# Satellite_Transceiver_Function_Board__Sw.net
KiCad netlist of a schematic drawn in EAGLE
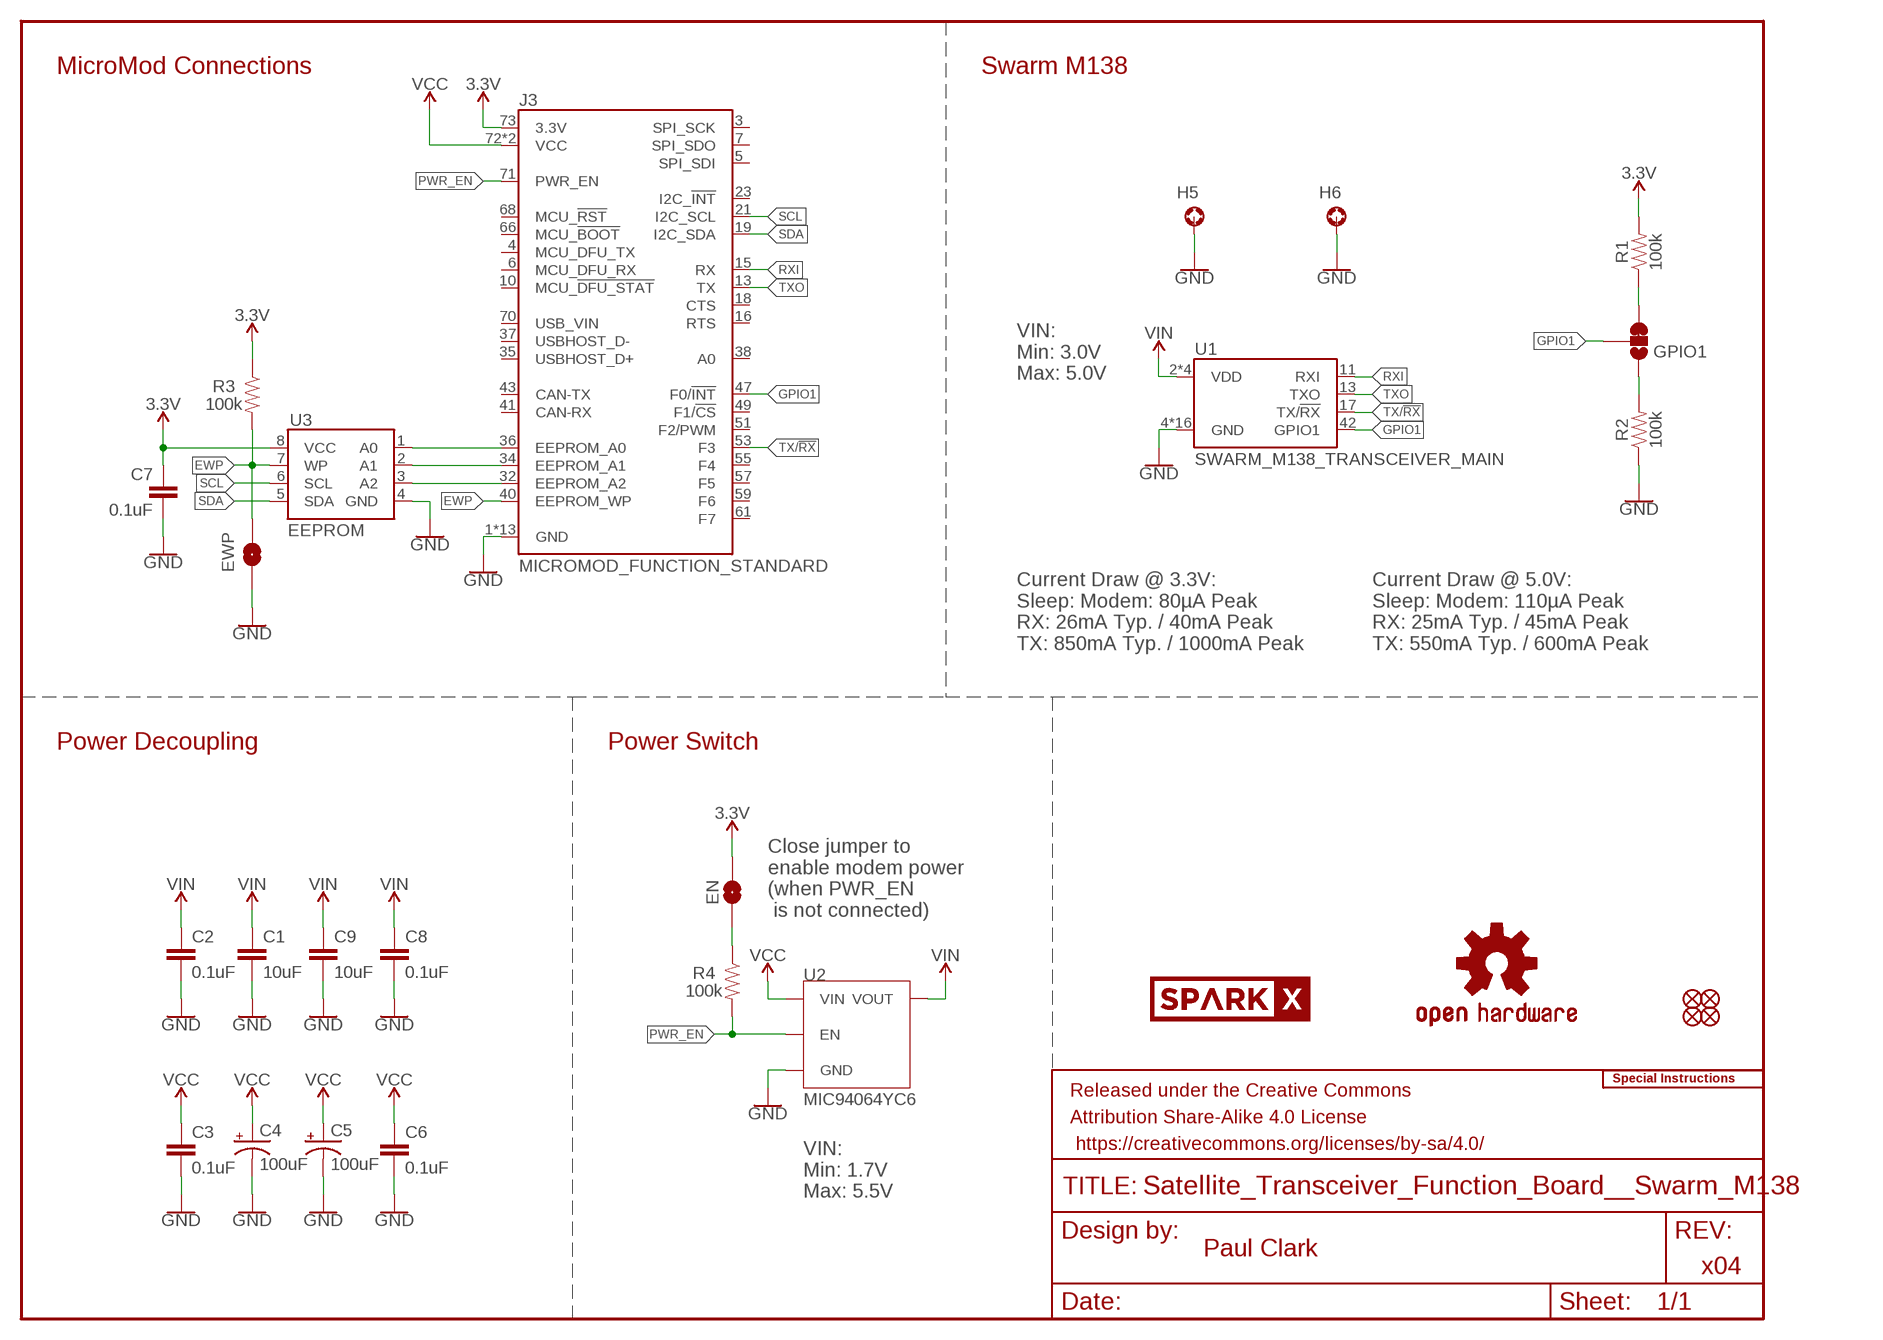
[diagram p0: schematic, sheet 1]

(export (version "E")
  (design (tool "Eeschema 10.0.6"))
  (components
    (comp (ref "C1")
      (value "10uF")
      (footprint "eagle-import:0603")
      (libsource (lib "eagle-import") (part "10UF-0603-6.3V-20%"))
    )
    (comp (ref "C2")
      (value "0.1uF")
      (footprint "eagle-import:0603")
      (libsource (lib "eagle-import") (part "0.1UF-0603-25V-5%"))
    )
    (comp (ref "C3")
      (value "0.1uF")
      (footprint "eagle-import:0603")
      (libsource (lib "eagle-import") (part "0.1UF-0603-25V-5%"))
    )
    (comp (ref "C4")
      (value "100uF")
      (footprint "eagle-import:EIA3528")
      (libsource (lib "eagle-import") (part "100UF-POLAR-EIA3528-10V-20%(TANT)"))
    )
    (comp (ref "C5")
      (value "100uF")
      (footprint "eagle-import:EIA3528")
      (libsource (lib "eagle-import") (part "100UF-POLAR-EIA3528-10V-20%(TANT)"))
    )
    (comp (ref "C6")
      (value "0.1uF")
      (footprint "eagle-import:0603")
      (libsource (lib "eagle-import") (part "0.1UF-0603-25V-5%"))
    )
    (comp (ref "C7")
      (value "0.1uF")
      (footprint "eagle-import:0603")
      (libsource (lib "eagle-import") (part "0.1UF-0603-25V-5%"))
    )
    (comp (ref "C8")
      (value "0.1uF")
      (footprint "eagle-import:0603")
      (libsource (lib "eagle-import") (part "0.1UF-0603-25V-5%"))
    )
    (comp (ref "C9")
      (value "10uF")
      (footprint "eagle-import:0603")
      (libsource (lib "eagle-import") (part "10UF-0603-6.3V-20%"))
    )
    (comp (ref "EN")
      (value "JUMPER-SMT_2_NO_SILK")
      (footprint "eagle-import:SMT-JUMPER_2_NO_SILK")
      (libsource (lib "eagle-import") (part "JUMPER-SMT_2_NO_SILK"))
    )
    (comp (ref "EWP")
      (value "JUMPER-SMT_2_NO_SILK")
      (footprint "eagle-import:SMT-JUMPER_2_NO_SILK")
      (libsource (lib "eagle-import") (part "JUMPER-SMT_2_NO_SILK"))
    )
    (comp (ref "FD1")
      (value "FIDUCIAL1X2")
      (footprint "eagle-import:FIDUCIAL-1X2")
      (libsource (lib "eagle-import") (part "FIDUCIAL1X2"))
    )
    (comp (ref "FD2")
      (value "FIDUCIAL1X2")
      (footprint "eagle-import:FIDUCIAL-1X2")
      (libsource (lib "eagle-import") (part "FIDUCIAL1X2"))
    )
    (comp (ref "FD3")
      (value "FIDUCIAL1X2")
      (footprint "eagle-import:FIDUCIAL-1X2")
      (libsource (lib "eagle-import") (part "FIDUCIAL1X2"))
    )
    (comp (ref "FD4")
      (value "FIDUCIAL1X2")
      (footprint "eagle-import:FIDUCIAL-1X2")
      (libsource (lib "eagle-import") (part "FIDUCIAL1X2"))
    )
    (comp (ref "FRAME1")
      (value "FRAME-LETTER")
      (footprint "eagle-import:CREATIVE_COMMONS")
      (libsource (lib "eagle-import") (part "FRAME-LETTER"))
    )
    (comp (ref "GPIO1")
      (value "JUMPER-SMT_3_1-NC_TRACE_SILK")
      (footprint "eagle-import:SMT-JUMPER_3_1-NC_TRACE_SILK")
      (libsource (lib "eagle-import") (part "JUMPER-SMT_3_1-NC_TRACE_SILK"))
    )
    (comp (ref "H5")
      (value "STAND-OFF-REFLOW-M2.5_1.5MM_TALL")
      (footprint "eagle-import:STAND-OFF-REFLOW-M2.5")
      (libsource (lib "eagle-import") (part "STAND-OFF-REFLOW-M2.5_1.5MM_TALL"))
    )
    (comp (ref "H6")
      (value "STAND-OFF-REFLOW-M2.5_1.5MM_TALL")
      (footprint "eagle-import:STAND-OFF-REFLOW-M2.5")
      (libsource (lib "eagle-import") (part "STAND-OFF-REFLOW-M2.5_1.5MM_TALL"))
    )
    (comp (ref "J3")
      (value "MICROMOD_FUNCTION_STANDARD")
      (footprint "eagle-import:M.2-CARD-E-22_FUNCTION_STANDARD")
      (libsource (lib "eagle-import") (part "MICROMOD_FUNCTION_STANDARD"))
    )
    (comp (ref "LOGO1")
      (value "SPECIAL_INSTRUCTIONS-ORDERING")
      (footprint "eagle-import:ORDERING_INSTRUCTIONS")
      (libsource (lib "eagle-import") (part "SPECIAL_INSTRUCTIONS-ORDERING"))
    )
    (comp (ref "LOGO2")
      (value "OSHW-LOGOS")
      (footprint "eagle-import:OSHW-LOGO-S")
      (libsource (lib "eagle-import") (part "OSHW-LOGOS"))
    )
    (comp (ref "R1")
      (value "100k")
      (footprint "eagle-import:0603")
      (libsource (lib "eagle-import") (part "100KOHM-0603-1/10W-1%"))
    )
    (comp (ref "R2")
      (value "100k")
      (footprint "eagle-import:0603")
      (libsource (lib "eagle-import") (part "100KOHM-0603-1/10W-1%"))
    )
    (comp (ref "R3")
      (value "100k")
      (footprint "eagle-import:0603")
      (libsource (lib "eagle-import") (part "100KOHM-0603-1/10W-1%"))
    )
    (comp (ref "R4")
      (value "100k")
      (footprint "eagle-import:0603")
      (libsource (lib "eagle-import") (part "100KOHM-0603-1/10W-1%"))
    )
    (comp (ref "U$1")
      (value "SPARKX-LOGO5")
      (footprint "eagle-import:SPARKX-LARGE")
      (libsource (lib "eagle-import") (part "SPARKX-LOGO5"))
    )
    (comp (ref "U$2")
      (value "SPARKX-LOGO5")
      (footprint "eagle-import:SPARKX-LARGE")
      (libsource (lib "eagle-import") (part "SPARKX-LOGO5"))
    )
    (comp (ref "U1")
      (value "SWARM_M138_TRANSCEIVER_MAIN")
      (footprint "eagle-import:M.2-SWARM-M138-A")
      (libsource (lib "eagle-import") (part "SWARM_M138_TRANSCEIVER_MAIN"))
    )
    (comp (ref "U2")
      (value "MIC94064YC6")
      (footprint "eagle-import:SC-70-6")
      (libsource (lib "eagle-import") (part "MIC94064/5_MIC94064YC6"))
    )
    (comp (ref "U3")
      (value "EEPROM")
      (footprint "eagle-import:SO08")
      (libsource (lib "eagle-import") (part "EEPROM-I2C512K"))
    )
  )
  (nets
    (net (code "1") (name "/TX{slash}~{RX}") (class "Default")
      (node (ref "J3") (pin "53") (pinfunction "F3_53") (pintype "bidirectional"))
      (node (ref "U1") (pin "17") (pinfunction "TX/~{RX}_17") (pintype "output"))
    )
    (net (code "2") (name "3.3V") (class "Default")
      (node (ref "C7") (pin "1") (pinfunction "1_1") (pintype "passive"))
      (node (ref "EN") (pin "2") (pinfunction "2_2") (pintype "passive"))
      (node (ref "J3") (pin "73") (pinfunction "3.3V_73") (pintype "bidirectional"))
      (node (ref "R1") (pin "2") (pinfunction "2_2") (pintype "passive"))
      (node (ref "R3") (pin "1") (pinfunction "1_1") (pintype "passive"))
      (node (ref "U3") (pin "8") (pinfunction "VCC_8") (pintype "power_in"))
    )
    (net (code "3") (name "EWP") (class "Default")
      (node (ref "EWP") (pin "2") (pinfunction "2_2") (pintype "passive"))
      (node (ref "J3") (pin "40") (pinfunction "EEPROM_WP_40") (pintype "bidirectional"))
      (node (ref "R3") (pin "2") (pinfunction "2_2") (pintype "passive"))
      (node (ref "U3") (pin "7") (pinfunction "WP_7") (pintype "bidirectional"))
    )
    (net (code "4") (name "GND") (class "Default")
      (node (ref "C1") (pin "2") (pinfunction "2_2") (pintype "passive"))
      (node (ref "C2") (pin "2") (pinfunction "2_2") (pintype "passive"))
      (node (ref "C3") (pin "2") (pinfunction "2_2") (pintype "passive"))
      (node (ref "C4") (pin "C") (pinfunction "-_C") (pintype "passive"))
      (node (ref "C5") (pin "C") (pinfunction "-_C") (pintype "passive"))
      (node (ref "C6") (pin "2") (pinfunction "2_2") (pintype "passive"))
      (node (ref "C7") (pin "2") (pinfunction "2_2") (pintype "passive"))
      (node (ref "C8") (pin "2") (pinfunction "2_2") (pintype "passive"))
      (node (ref "C9") (pin "2") (pinfunction "2_2") (pintype "passive"))
      (node (ref "EWP") (pin "1") (pinfunction "1_1") (pintype "passive"))
      (node (ref "H5") (pin "1") (pinfunction "1_1") (pintype "bidirectional"))
      (node (ref "H6") (pin "1") (pinfunction "1_1") (pintype "bidirectional"))
      (node (ref "J3") (pin "1") (pinfunction "GND_1") (pintype "bidirectional"))
      (node (ref "J3") (pin "2") (pinfunction "GND_2") (pintype "bidirectional"))
      (node (ref "J3") (pin "33") (pinfunction "GND_33") (pintype "bidirectional"))
      (node (ref "J3") (pin "39") (pinfunction "GND_39") (pintype "bidirectional"))
      (node (ref "J3") (pin "45") (pinfunction "GND_45") (pintype "bidirectional"))
      (node (ref "J3") (pin "75") (pinfunction "GND_75") (pintype "bidirectional"))
      (node (ref "J3") (pin "8") (pinfunction "GND_8") (pintype "bidirectional"))
      (node (ref "J3") (pin "GND1") (pinfunction "GND_GND1") (pintype "bidirectional"))
      (node (ref "J3") (pin "GND2") (pinfunction "GND_GND2") (pintype "bidirectional"))
      (node (ref "J3") (pin "GND3") (pinfunction "GND_GND3") (pintype "bidirectional"))
      (node (ref "J3") (pin "GND4") (pinfunction "GND_GND4") (pintype "bidirectional"))
      (node (ref "J3") (pin "GND5") (pinfunction "GND_GND5") (pintype "bidirectional"))
      (node (ref "J3") (pin "GND6") (pinfunction "GND_GND6") (pintype "bidirectional"))
      (node (ref "R2") (pin "1") (pinfunction "1_1") (pintype "passive"))
      (node (ref "U1") (pin "15") (pinfunction "GND_15") (pintype "power_in"))
      (node (ref "U1") (pin "18") (pinfunction "GND_18") (pintype "power_in"))
      (node (ref "U1") (pin "21") (pinfunction "GND_21") (pintype "power_in"))
      (node (ref "U1") (pin "26") (pinfunction "GND_26") (pintype "power_in"))
      (node (ref "U1") (pin "27") (pinfunction "GND_27") (pintype "power_in"))
      (node (ref "U1") (pin "29") (pinfunction "GND_29") (pintype "power_in"))
      (node (ref "U1") (pin "34") (pinfunction "GND_34") (pintype "power_in"))
      (node (ref "U1") (pin "35") (pinfunction "GND_35") (pintype "power_in"))
      (node (ref "U1") (pin "37") (pinfunction "GND_37") (pintype "power_in"))
      (node (ref "U1") (pin "4") (pinfunction "GND_4") (pintype "power_in"))
      (node (ref "U1") (pin "40") (pinfunction "GND_40") (pintype "power_in"))
      (node (ref "U1") (pin "43") (pinfunction "GND_43") (pintype "power_in"))
      (node (ref "U1") (pin "50") (pinfunction "GND_50") (pintype "power_in"))
      (node (ref "U1") (pin "9") (pinfunction "GND_9") (pintype "power_in"))
      (node (ref "U1") (pin "A1") (pinfunction "GND_A1") (pintype "power_in"))
      (node (ref "U1") (pin "A2") (pinfunction "GND_A2") (pintype "power_in"))
      (node (ref "U2") (pin "2") (pinfunction "GND_2") (pintype "power_in"))
      (node (ref "U2") (pin "5") (pinfunction "GND_5") (pintype "power_in"))
      (node (ref "U3") (pin "4") (pinfunction "GND_4") (pintype "power_in"))
    )
    (net (code "5") (name "GPIO1") (class "Default")
      (node (ref "GPIO1") (pin "2") (pinfunction "2_2") (pintype "passive"))
      (node (ref "J3") (pin "47") (pinfunction "F0/~{INT}_47") (pintype "bidirectional"))
      (node (ref "U1") (pin "42") (pinfunction "GPIO1_42") (pintype "bidirectional"))
    )
    (net (code "6") (name "Net-(EN-Pad1)") (class "Default")
      (node (ref "EN") (pin "1") (pinfunction "1_1") (pintype "passive"))
      (node (ref "R4") (pin "1") (pinfunction "1_1") (pintype "passive"))
    )
    (net (code "7") (name "Net-(GPIO1-Pad1)") (class "Default")
      (node (ref "GPIO1") (pin "1") (pinfunction "1_1") (pintype "passive"))
      (node (ref "R2") (pin "2") (pinfunction "2_2") (pintype "passive"))
    )
    (net (code "8") (name "Net-(GPIO1-Pad3)") (class "Default")
      (node (ref "GPIO1") (pin "3") (pinfunction "3_3") (pintype "passive"))
      (node (ref "R1") (pin "1") (pinfunction "1_1") (pintype "passive"))
    )
    (net (code "9") (name "Net-(J3-EEPROM_A0)") (class "Default")
      (node (ref "J3") (pin "36") (pinfunction "EEPROM_A0_36") (pintype "bidirectional"))
      (node (ref "U3") (pin "1") (pinfunction "A0_1") (pintype "bidirectional"))
    )
    (net (code "10") (name "Net-(J3-EEPROM_A1)") (class "Default")
      (node (ref "J3") (pin "34") (pinfunction "EEPROM_A1_34") (pintype "bidirectional"))
      (node (ref "U3") (pin "2") (pinfunction "A1_2") (pintype "bidirectional"))
    )
    (net (code "11") (name "Net-(J3-EEPROM_A2)") (class "Default")
      (node (ref "J3") (pin "32") (pinfunction "EEPROM_A2_32") (pintype "bidirectional"))
      (node (ref "U3") (pin "3") (pinfunction "A2_3") (pintype "bidirectional"))
    )
    (net (code "12") (name "PWR_EN") (class "Default")
      (node (ref "J3") (pin "71") (pinfunction "PWR_EN_71") (pintype "bidirectional"))
      (node (ref "R4") (pin "2") (pinfunction "2_2") (pintype "passive"))
      (node (ref "U2") (pin "3") (pinfunction "EN_3") (pintype "input"))
    )
    (net (code "13") (name "RXI") (class "Default")
      (node (ref "J3") (pin "15") (pinfunction "RX_15") (pintype "bidirectional"))
      (node (ref "U1") (pin "11") (pinfunction "RXI_11") (pintype "input"))
    )
    (net (code "14") (name "SCL") (class "Default")
      (node (ref "J3") (pin "21") (pinfunction "I2C_SCL_21") (pintype "bidirectional"))
      (node (ref "U3") (pin "6") (pinfunction "SCL_6") (pintype "bidirectional"))
    )
    (net (code "15") (name "SDA") (class "Default")
      (node (ref "J3") (pin "19") (pinfunction "I2C_SDA_19") (pintype "bidirectional"))
      (node (ref "U3") (pin "5") (pinfunction "SDA_5") (pintype "bidirectional"))
    )
    (net (code "16") (name "TXO") (class "Default")
      (node (ref "J3") (pin "13") (pinfunction "TX_13") (pintype "bidirectional"))
      (node (ref "U1") (pin "13") (pinfunction "TXO_13") (pintype "output"))
    )
    (net (code "17") (name "VCC") (class "Default")
      (node (ref "C3") (pin "1") (pinfunction "1_1") (pintype "passive"))
      (node (ref "C4") (pin "A") (pinfunction "+_A") (pintype "passive"))
      (node (ref "C5") (pin "A") (pinfunction "+_A") (pintype "passive"))
      (node (ref "C6") (pin "1") (pinfunction "1_1") (pintype "passive"))
      (node (ref "J3") (pin "72") (pinfunction "VCC_72") (pintype "bidirectional"))
      (node (ref "J3") (pin "74") (pinfunction "VCC_74") (pintype "bidirectional"))
      (node (ref "U2") (pin "4") (pinfunction "VIN_4") (pintype "power_in"))
    )
    (net (code "18") (name "VIN") (class "Default")
      (node (ref "C1") (pin "1") (pinfunction "1_1") (pintype "passive"))
      (node (ref "C2") (pin "1") (pinfunction "1_1") (pintype "passive"))
      (node (ref "C8") (pin "1") (pinfunction "1_1") (pintype "passive"))
      (node (ref "C9") (pin "1") (pinfunction "1_1") (pintype "passive"))
      (node (ref "U1") (pin "2") (pinfunction "VDD_2") (pintype "power_in"))
      (node (ref "U1") (pin "39") (pinfunction "VDD_39") (pintype "power_in"))
      (node (ref "U1") (pin "41") (pinfunction "VDD_41") (pintype "power_in"))
      (node (ref "U1") (pin "52") (pinfunction "VDD_52") (pintype "power_in"))
      (node (ref "U2") (pin "1") (pinfunction "VOUT_1") (pintype "power_in"))
    )
    (net (code "19") (name "unconnected-(J3-A0-Pad38)") (class "Default")
      (node (ref "J3") (pin "38") (pinfunction "A0_38") (pintype "bidirectional"))
    )
    (net (code "20") (name "unconnected-(J3-CAN-RX-Pad41)") (class "Default")
      (node (ref "J3") (pin "41") (pinfunction "CAN-RX_41") (pintype "bidirectional"))
    )
    (net (code "21") (name "unconnected-(J3-CAN-TX-Pad43)") (class "Default")
      (node (ref "J3") (pin "43") (pinfunction "CAN-TX_43") (pintype "bidirectional"))
    )
    (net (code "22") (name "unconnected-(J3-CTS-Pad18)") (class "Default")
      (node (ref "J3") (pin "18") (pinfunction "CTS_18") (pintype "bidirectional"))
    )
    (net (code "23") (name "unconnected-(J3-F1{slash}~{CS}-Pad49)") (class "Default")
      (node (ref "J3") (pin "49") (pinfunction "F1/~{CS}_49") (pintype "bidirectional"))
    )
    (net (code "24") (name "unconnected-(J3-F2{slash}PWM-Pad51)") (class "Default")
      (node (ref "J3") (pin "51") (pinfunction "F2/PWM_51") (pintype "bidirectional"))
    )
    (net (code "25") (name "unconnected-(J3-F4-Pad55)") (class "Default")
      (node (ref "J3") (pin "55") (pinfunction "F4_55") (pintype "bidirectional"))
    )
    (net (code "26") (name "unconnected-(J3-F5-Pad57)") (class "Default")
      (node (ref "J3") (pin "57") (pinfunction "F5_57") (pintype "bidirectional"))
    )
    (net (code "27") (name "unconnected-(J3-F6-Pad59)") (class "Default")
      (node (ref "J3") (pin "59") (pinfunction "F6_59") (pintype "bidirectional"))
    )
    (net (code "28") (name "unconnected-(J3-F7-Pad61)") (class "Default")
      (node (ref "J3") (pin "61") (pinfunction "F7_61") (pintype "bidirectional"))
    )
    (net (code "29") (name "unconnected-(J3-I2C_~{INT}-Pad23)") (class "Default")
      (node (ref "J3") (pin "23") (pinfunction "I2C_~{INT}_23") (pintype "bidirectional"))
    )
    (net (code "30") (name "unconnected-(J3-MCU_DFU_RX-Pad6)") (class "Default")
      (node (ref "J3") (pin "6") (pinfunction "MCU_DFU_RX_6") (pintype "bidirectional"))
    )
    (net (code "31") (name "unconnected-(J3-MCU_DFU_TX-Pad4)") (class "Default")
      (node (ref "J3") (pin "4") (pinfunction "MCU_DFU_TX_4") (pintype "bidirectional"))
    )
    (net (code "32") (name "unconnected-(J3-MCU_~{BOOT}-Pad66)") (class "Default")
      (node (ref "J3") (pin "66") (pinfunction "MCU_~{BOOT}_66") (pintype "bidirectional"))
    )
    (net (code "33") (name "unconnected-(J3-MCU_~{DFU_STAT}-Pad10)") (class "Default")
      (node (ref "J3") (pin "10") (pinfunction "MCU_~{DFU_STAT}_10") (pintype "bidirectional"))
    )
    (net (code "34") (name "unconnected-(J3-MCU_~{RST}-Pad68)") (class "Default")
      (node (ref "J3") (pin "68") (pinfunction "MCU_~{RST}_68") (pintype "bidirectional"))
    )
    (net (code "35") (name "unconnected-(J3-RTS-Pad16)") (class "Default")
      (node (ref "J3") (pin "16") (pinfunction "RTS_16") (pintype "bidirectional"))
    )
    (net (code "36") (name "unconnected-(J3-SPI_SCK-Pad3)") (class "Default")
      (node (ref "J3") (pin "3") (pinfunction "SPI_SCK_3") (pintype "bidirectional"))
    )
    (net (code "37") (name "unconnected-(J3-SPI_SDI-Pad5)") (class "Default")
      (node (ref "J3") (pin "5") (pinfunction "SPI_SDI_5") (pintype "bidirectional"))
    )
    (net (code "38") (name "unconnected-(J3-SPI_SDO-Pad7)") (class "Default")
      (node (ref "J3") (pin "7") (pinfunction "SPI_SDO_7") (pintype "bidirectional"))
    )
    (net (code "39") (name "unconnected-(J3-USBHOST_D+-Pad35)") (class "Default")
      (node (ref "J3") (pin "35") (pinfunction "USBHOST_D+_35") (pintype "bidirectional"))
    )
    (net (code "40") (name "unconnected-(J3-USBHOST_D--Pad37)") (class "Default")
      (node (ref "J3") (pin "37") (pinfunction "USBHOST_D-_37") (pintype "bidirectional"))
    )
    (net (code "41") (name "unconnected-(J3-USB_VIN-Pad70)") (class "Default")
      (node (ref "J3") (pin "70") (pinfunction "USB_VIN_70") (pintype "bidirectional"))
    )
  )
)
